# ActuatorCan.net
KiCad netlist of a schematic drawn in Altium Designer
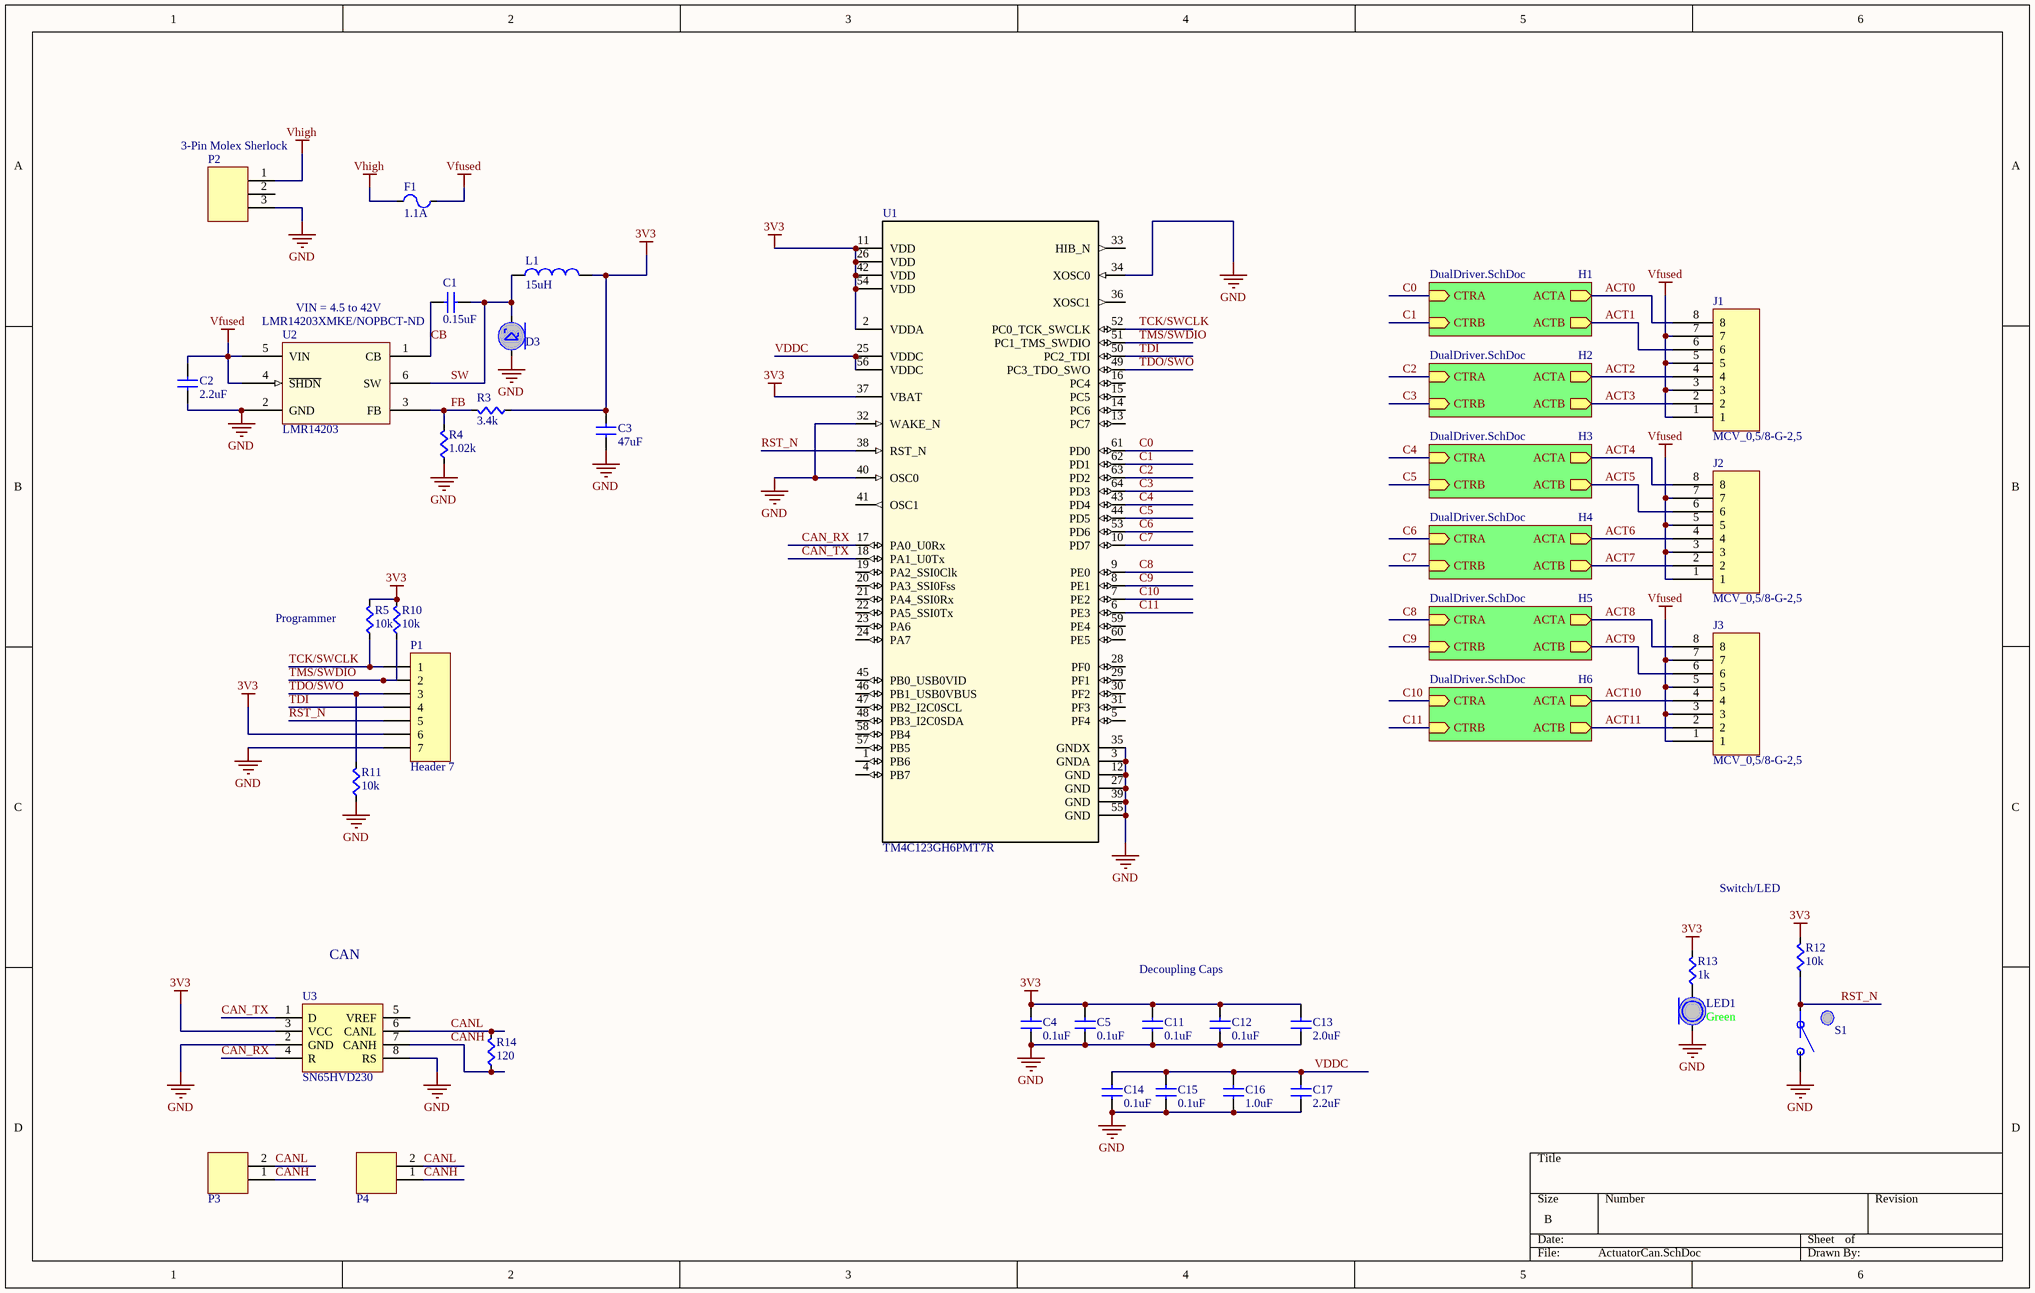
[diagram p0: ActuatorCan.SchDoc]

(export (version "E")
  (design (tool "Eeschema 10.0.6"))
  (components
    (comp (ref "C1")
      (value "0.15uF")
      (footprint "CAPC0603")
      (fields (field (name "Comment") "Cap"))
      (libsource (lib "Passives") (part "Cap"))
    )
    (comp (ref "C2")
      (value "2.2uF")
      (footprint "CAPC0805")
      (fields (field (name "Comment") "Cap"))
      (libsource (lib "Passives") (part "Cap"))
    )
    (comp (ref "C3")
      (value "47uF")
      (footprint "CAPC1206")
      (fields (field (name "Comment") "Cap"))
      (libsource (lib "Passives") (part "Cap"))
    )
    (comp (ref "C4")
      (value "0.1uF")
      (footprint "CAPC0603")
      (fields (field (name "Comment") "Cap"))
      (libsource (lib "SubjuGator8") (part "Cap"))
    )
    (comp (ref "C5")
      (value "0.1uF")
      (footprint "CAPC0603")
      (fields (field (name "Comment") "Cap"))
      (libsource (lib "SubjuGator8") (part "Cap"))
    )
    (comp (ref "C11")
      (value "0.1uF")
      (footprint "CAPC0603")
      (fields (field (name "Comment") "Cap"))
      (libsource (lib "SubjuGator8") (part "Cap"))
    )
    (comp (ref "C12")
      (value "0.1uF")
      (footprint "CAPC0603")
      (fields (field (name "Comment") "Cap"))
      (libsource (lib "SubjuGator8") (part "Cap"))
    )
    (comp (ref "C13")
      (value "2.0uF")
      (footprint "CAPC0603")
      (fields (field (name "Comment") "Cap"))
      (libsource (lib "SubjuGator8") (part "Cap"))
    )
    (comp (ref "C14")
      (value "0.1uF")
      (footprint "CAPC0603")
      (fields (field (name "Comment") "Cap"))
      (libsource (lib "SubjuGator8") (part "Cap"))
    )
    (comp (ref "C15")
      (value "0.1uF")
      (footprint "CAPC0603")
      (fields (field (name "Comment") "Cap"))
      (libsource (lib "SubjuGator8") (part "Cap"))
    )
    (comp (ref "C16")
      (value "1.0uF")
      (footprint "CAPC0603")
      (fields (field (name "Comment") "Cap"))
      (libsource (lib "SubjuGator8") (part "Cap"))
    )
    (comp (ref "C17")
      (value "2.2uF")
      (footprint "CAPC0603")
      (fields (field (name "Comment") "Cap"))
      (libsource (lib "SubjuGator8") (part "Cap"))
    )
    (comp (ref "D3")
      (value "Schottky")
      (footprint "1N5819HW-7-F")
      (description "Schottky Diode Template")
      (libsource (lib "Semiconductors") (part "Schottky"))
    )
    (comp (ref "F1")
      (value "1.1A")
      (footprint "PTC7451X11N")
      (fields (field (name "Comment") "PTC Fuse"))
      (libsource (lib "Passives") (part "PTC_Fuse"))
    )
    (comp (ref "J1")
      (value "MCV_0,5/8-G-2,5")
      (footprint "MCV_0,5/8-G-2,5")
      (description "CONN TERM BLOCK 2.50MM 8POS, Vertical, Through-Hole, 4A")
      (libsource (lib "Connectors") (part "MCV_0,5/8-G-2,5"))
    )
    (comp (ref "J2")
      (value "MCV_0,5/8-G-2,5")
      (footprint "MCV_0,5/8-G-2,5")
      (description "CONN TERM BLOCK 2.50MM 8POS, Vertical, Through-Hole, 4A")
      (libsource (lib "Connectors") (part "MCV_0,5/8-G-2,5"))
    )
    (comp (ref "J3")
      (value "MCV_0,5/8-G-2,5")
      (footprint "MCV_0,5/8-G-2,5")
      (description "CONN TERM BLOCK 2.50MM 8POS, Vertical, Through-Hole, 4A")
      (libsource (lib "Connectors") (part "MCV_0,5/8-G-2,5"))
    )
    (comp (ref "L1")
      (value "Inductor")
      (footprint "NS10165T150MNA")
      (fields (field (name "INDUCTANCE") "15uH"))
      (libsource (lib "Passives") (part "Inductor"))
    )
    (comp (ref "LED1")
      (value "LED")
      (footprint "LED0603")
      (fields (field (name "COLOR") "Green"))
      (libsource (lib "SubjuGator8") (part "LED"))
    )
    (comp (ref "P1")
      (value "Header 7")
      (footprint "HDR1X7")
      (description "Header, 7-Pin")
      (fields (field (name "PUBLISHER") "Altium Limited"))
      (libsource (lib "Miscellaneous Connectors") (part "Header 7"))
    )
    (comp (ref "P2")
      (value "3-Pin Molex Sherlock")
      (footprint "MOLEX-HDR-1X3-SHERLOCK-VERT")
      (libsource (lib "SubjuGator8") (part "MOLEX-HDR-1x3-SHERLOCK_VERT"))
    )
    (comp (ref "P3")
      (value "2-pin Horz Sherlock")
      (footprint "MOLEX-HDR-1X2-SHERLOCK-HORZ")
      (fields
        (field (name "MANUFACTURER PART NUMBER") "0353630260")
        (field (name "MANUFACTURER") "Molex Inc")
      )
      (libsource (lib "SubjuGator8") (part "MOLEX-HDR-1x2-SHERLOCK_RA"))
    )
    (comp (ref "P4")
      (value "2-pin Horz Sherlock")
      (footprint "MOLEX-HDR-1X2-SHERLOCK-HORZ")
      (fields
        (field (name "MANUFACTURER PART NUMBER") "0353630260")
        (field (name "MANUFACTURER") "Molex Inc")
      )
      (libsource (lib "SubjuGator8") (part "MOLEX-HDR-1x2-SHERLOCK_RA"))
    )
    (comp (ref "R3")
      (value "3.4k")
      (footprint "RES0603")
      (fields (field (name "Comment") "Res"))
      (libsource (lib "Passives") (part "Res"))
    )
    (comp (ref "R4")
      (value "1.02k")
      (footprint "RES0603")
      (fields (field (name "Comment") "Res"))
      (libsource (lib "Passives") (part "Res"))
    )
    (comp (ref "R5")
      (value "10k")
      (footprint "RES0603")
      (fields (field (name "Comment") "Res"))
      (libsource (lib "SubjuGator8") (part "Res"))
    )
    (comp (ref "R10")
      (value "10k")
      (footprint "RES0603")
      (fields (field (name "Comment") "Res"))
      (libsource (lib "SubjuGator8") (part "Res"))
    )
    (comp (ref "R11")
      (value "10k")
      (footprint "RES0603")
      (fields (field (name "Comment") "Res"))
      (libsource (lib "SubjuGator8") (part "Res"))
    )
    (comp (ref "R12")
      (value "10k")
      (footprint "RES0603")
      (fields (field (name "Comment") "Res"))
      (libsource (lib "SubjuGator8") (part "Res"))
    )
    (comp (ref "R13")
      (value "1k")
      (footprint "RES0603")
      (fields (field (name "Comment") "Res"))
      (libsource (lib "SubjuGator8") (part "Res"))
    )
    (comp (ref "R14")
      (value "120")
      (footprint "RES0603")
      (fields (field (name "Comment") "Res"))
      (libsource (lib "SubjuGator8") (part "Res"))
    )
    (comp (ref "S1")
      (value "Button")
      (footprint "PTS645xxxxSMTR92")
      (description "SPST Button")
      (libsource (lib "SubjuGator8") (part "Button"))
    )
    (comp (ref "U1")
      (value "TM4C123GH6PMT7R")
      (footprint "PM0064A_N")
      (description "Imported")
      (fields
        (field (name "PARTNUMBER") "TM4C123GH6PMTR")
        (field (name "ALTERNATE_PARTNUMBER") "TM4C123GH6PMT")
      )
      (libsource (lib "2018-10-31_17-53-54") (part "TM4C123GH6PMT7R"))
    )
    (comp (ref "U2")
      (value "LMR14203")
      (footprint "SOT95P280X110-6N")
      (description "Simple Switcher 42Vin 0.3A Step-Down Voltage Regulator")
      (fields (field (name "SUPPLIER PART NUMBER 1") "LMR14203XMKE/NOPBCT-ND"))
      (libsource (lib "ICs") (part "LMR14203"))
    )
    (comp (ref "U3")
      (value "SN65HVD230")
      (footprint "SOIC-8pin")
      (description "3.3V CAN Bus Transceiver")
      (libsource (lib "SubjuGator8") (part "SN65HVD230"))
    )
  )
  (nets
    (net (code "1") (name "/ACT0") (class "Default")
      (node (ref "J1") (pin "8") (pinfunction "8_8") (pintype "passive"))
    )
    (net (code "2") (name "/ACT1") (class "Default")
      (node (ref "J1") (pin "6") (pinfunction "6_6") (pintype "passive"))
    )
    (net (code "3") (name "/ACT2") (class "Default")
      (node (ref "J1") (pin "4") (pinfunction "4_4") (pintype "passive"))
    )
    (net (code "4") (name "/ACT3") (class "Default")
      (node (ref "J1") (pin "2") (pinfunction "2_2") (pintype "passive"))
    )
    (net (code "5") (name "/ACT4") (class "Default")
      (node (ref "J2") (pin "8") (pinfunction "8_8") (pintype "passive"))
    )
    (net (code "6") (name "/ACT5") (class "Default")
      (node (ref "J2") (pin "6") (pinfunction "6_6") (pintype "passive"))
    )
    (net (code "7") (name "/ACT6") (class "Default")
      (node (ref "J2") (pin "4") (pinfunction "4_4") (pintype "passive"))
    )
    (net (code "8") (name "/ACT7") (class "Default")
      (node (ref "J2") (pin "2") (pinfunction "2_2") (pintype "passive"))
    )
    (net (code "9") (name "/ACT8") (class "Default")
      (node (ref "J3") (pin "8") (pinfunction "8_8") (pintype "passive"))
    )
    (net (code "10") (name "/ACT9") (class "Default")
      (node (ref "J3") (pin "6") (pinfunction "6_6") (pintype "passive"))
    )
    (net (code "11") (name "/ACT10") (class "Default")
      (node (ref "J3") (pin "4") (pinfunction "4_4") (pintype "passive"))
    )
    (net (code "12") (name "/ACT11") (class "Default")
      (node (ref "J3") (pin "2") (pinfunction "2_2") (pintype "passive"))
    )
    (net (code "13") (name "/C0") (class "Default")
      (node (ref "U1") (pin "61") (pinfunction "PD0_61") (pintype "bidirectional"))
    )
    (net (code "14") (name "/C1") (class "Default")
      (node (ref "U1") (pin "62") (pinfunction "PD1_62") (pintype "bidirectional"))
    )
    (net (code "15") (name "/C2") (class "Default")
      (node (ref "U1") (pin "63") (pinfunction "PD2_63") (pintype "bidirectional"))
    )
    (net (code "16") (name "/C3") (class "Default")
      (node (ref "U1") (pin "64") (pinfunction "PD3_64") (pintype "bidirectional"))
    )
    (net (code "17") (name "/C4") (class "Default")
      (node (ref "U1") (pin "43") (pinfunction "PD4_43") (pintype "bidirectional"))
    )
    (net (code "18") (name "/C5") (class "Default")
      (node (ref "U1") (pin "44") (pinfunction "PD5_44") (pintype "bidirectional"))
    )
    (net (code "19") (name "/C6") (class "Default")
      (node (ref "U1") (pin "53") (pinfunction "PD6_53") (pintype "bidirectional"))
    )
    (net (code "20") (name "/C7") (class "Default")
      (node (ref "U1") (pin "10") (pinfunction "PD7_10") (pintype "bidirectional"))
    )
    (net (code "21") (name "/C8") (class "Default")
      (node (ref "U1") (pin "9") (pinfunction "PE0_9") (pintype "bidirectional"))
    )
    (net (code "22") (name "/C9") (class "Default")
      (node (ref "U1") (pin "8") (pinfunction "PE1_8") (pintype "bidirectional"))
    )
    (net (code "23") (name "/C10") (class "Default")
      (node (ref "U1") (pin "7") (pinfunction "PE2_7") (pintype "bidirectional"))
    )
    (net (code "24") (name "/C11") (class "Default")
      (node (ref "U1") (pin "6") (pinfunction "PE3_6") (pintype "bidirectional"))
    )
    (net (code "25") (name "/CANH") (class "Default")
      (node (ref "P3") (pin "1") (pinfunction "1_1") (pintype "passive"))
      (node (ref "P4") (pin "1") (pinfunction "1_1") (pintype "passive"))
      (node (ref "R14") (pin "2") (pinfunction "B_2") (pintype "passive"))
      (node (ref "U3") (pin "7") (pinfunction "CANH_7") (pintype "passive"))
    )
    (net (code "26") (name "/CANL") (class "Default")
      (node (ref "P3") (pin "2") (pinfunction "2_2") (pintype "passive"))
      (node (ref "P4") (pin "2") (pinfunction "2_2") (pintype "passive"))
      (node (ref "R14") (pin "1") (pinfunction "A_1") (pintype "passive"))
      (node (ref "U3") (pin "6") (pinfunction "CANL_6") (pintype "passive"))
    )
    (net (code "27") (name "/CAN_RX") (class "Default")
      (node (ref "U1") (pin "17") (pinfunction "PA0_U0Rx_17") (pintype "bidirectional"))
      (node (ref "U3") (pin "4") (pinfunction "R_4") (pintype "passive"))
    )
    (net (code "28") (name "/CAN_TX") (class "Default")
      (node (ref "U1") (pin "18") (pinfunction "PA1_U0Tx_18") (pintype "bidirectional"))
      (node (ref "U3") (pin "1") (pinfunction "D_1") (pintype "passive"))
    )
    (net (code "29") (name "/CB") (class "Default")
      (node (ref "C1") (pin "1") (pinfunction "A_1") (pintype "passive"))
      (node (ref "U2") (pin "1") (pinfunction "CB_1") (pintype "passive"))
    )
    (net (code "30") (name "/FB") (class "Default")
      (node (ref "R3") (pin "1") (pinfunction "A_1") (pintype "passive"))
      (node (ref "R4") (pin "1") (pinfunction "A_1") (pintype "passive"))
      (node (ref "U2") (pin "3") (pinfunction "FB_3") (pintype "passive"))
    )
    (net (code "31") (name "/RST_N") (class "Default")
      (node (ref "P1") (pin "5") (pinfunction "5_5") (pintype "passive"))
      (node (ref "R12") (pin "2") (pinfunction "B_2") (pintype "passive"))
      (node (ref "S1") (pin "A") (pinfunction "A_A") (pintype "passive"))
      (node (ref "U1") (pin "38") (pinfunction "RST_N_38") (pintype "input"))
    )
    (net (code "32") (name "/SW") (class "Default")
      (node (ref "C1") (pin "2") (pinfunction "B_2") (pintype "passive"))
      (node (ref "D3") (pin "C") (pinfunction "C_C") (pintype "passive"))
      (node (ref "L1") (pin "1") (pinfunction "A_1") (pintype "passive"))
      (node (ref "U2") (pin "6") (pinfunction "SW_6") (pintype "passive"))
    )
    (net (code "33") (name "/TCK{slash}SWCLK") (class "Default")
      (node (ref "P1") (pin "1") (pinfunction "1_1") (pintype "passive"))
      (node (ref "R5") (pin "2") (pinfunction "B_2") (pintype "passive"))
      (node (ref "U1") (pin "52") (pinfunction "PC0_TCK_SWCLK_52") (pintype "bidirectional"))
    )
    (net (code "34") (name "/TDI") (class "Default")
      (node (ref "P1") (pin "4") (pinfunction "4_4") (pintype "passive"))
      (node (ref "U1") (pin "50") (pinfunction "PC2_TDI_50") (pintype "bidirectional"))
    )
    (net (code "35") (name "/TDO{slash}SWO") (class "Default")
      (node (ref "P1") (pin "3") (pinfunction "3_3") (pintype "passive"))
      (node (ref "R11") (pin "1") (pinfunction "A_1") (pintype "passive"))
      (node (ref "U1") (pin "49") (pinfunction "PC3_TDO_SWO_49") (pintype "bidirectional"))
    )
    (net (code "36") (name "/TMS{slash}SWDIO") (class "Default")
      (node (ref "P1") (pin "2") (pinfunction "2_2") (pintype "passive"))
      (node (ref "R10") (pin "2") (pinfunction "B_2") (pintype "passive"))
      (node (ref "U1") (pin "51") (pinfunction "PC1_TMS_SWDIO_51") (pintype "bidirectional"))
    )
    (net (code "37") (name "/VDDC") (class "Default")
      (node (ref "C14") (pin "1") (pinfunction "A_1") (pintype "passive"))
      (node (ref "C15") (pin "1") (pinfunction "A_1") (pintype "passive"))
      (node (ref "C16") (pin "1") (pinfunction "A_1") (pintype "passive"))
      (node (ref "C17") (pin "1") (pinfunction "A_1") (pintype "passive"))
      (node (ref "U1") (pin "25") (pinfunction "VDDC_25") (pintype "power_in"))
      (node (ref "U1") (pin "56") (pinfunction "VDDC_56") (pintype "power_in"))
    )
    (net (code "38") (name "3V3") (class "Default")
      (node (ref "C11") (pin "1") (pinfunction "A_1") (pintype "passive"))
      (node (ref "C12") (pin "1") (pinfunction "A_1") (pintype "passive"))
      (node (ref "C13") (pin "1") (pinfunction "A_1") (pintype "passive"))
      (node (ref "C3") (pin "2") (pinfunction "B_2") (pintype "passive"))
      (node (ref "C4") (pin "1") (pinfunction "A_1") (pintype "passive"))
      (node (ref "C5") (pin "1") (pinfunction "A_1") (pintype "passive"))
      (node (ref "L1") (pin "2") (pinfunction "B_2") (pintype "passive"))
      (node (ref "P1") (pin "6") (pinfunction "6_6") (pintype "passive"))
      (node (ref "R10") (pin "1") (pinfunction "A_1") (pintype "passive"))
      (node (ref "R12") (pin "1") (pinfunction "A_1") (pintype "passive"))
      (node (ref "R13") (pin "1") (pinfunction "A_1") (pintype "passive"))
      (node (ref "R3") (pin "2") (pinfunction "B_2") (pintype "passive"))
      (node (ref "R5") (pin "1") (pinfunction "A_1") (pintype "passive"))
      (node (ref "U1") (pin "11") (pinfunction "VDD_11") (pintype "power_in"))
      (node (ref "U1") (pin "2") (pinfunction "VDDA_2") (pintype "power_in"))
      (node (ref "U1") (pin "26") (pinfunction "VDD_26") (pintype "power_in"))
      (node (ref "U1") (pin "37") (pinfunction "VBAT_37") (pintype "power_in"))
      (node (ref "U1") (pin "42") (pinfunction "VDD_42") (pintype "power_in"))
      (node (ref "U1") (pin "54") (pinfunction "VDD_54") (pintype "power_in"))
      (node (ref "U3") (pin "3") (pinfunction "VCC_3") (pintype "passive"))
    )
    (net (code "39") (name "GND") (class "Default")
      (node (ref "C11") (pin "2") (pinfunction "B_2") (pintype "passive"))
      (node (ref "C12") (pin "2") (pinfunction "B_2") (pintype "passive"))
      (node (ref "C13") (pin "2") (pinfunction "B_2") (pintype "passive"))
      (node (ref "C14") (pin "2") (pinfunction "B_2") (pintype "passive"))
      (node (ref "C15") (pin "2") (pinfunction "B_2") (pintype "passive"))
      (node (ref "C16") (pin "2") (pinfunction "B_2") (pintype "passive"))
      (node (ref "C17") (pin "2") (pinfunction "B_2") (pintype "passive"))
      (node (ref "C2") (pin "1") (pinfunction "A_1") (pintype "passive"))
      (node (ref "C3") (pin "1") (pinfunction "A_1") (pintype "passive"))
      (node (ref "C4") (pin "2") (pinfunction "B_2") (pintype "passive"))
      (node (ref "C5") (pin "2") (pinfunction "B_2") (pintype "passive"))
      (node (ref "D3") (pin "A") (pinfunction "A_A") (pintype "passive"))
      (node (ref "LED1") (pin "C") (pinfunction "C_C") (pintype "passive"))
      (node (ref "P1") (pin "7") (pinfunction "7_7") (pintype "passive"))
      (node (ref "P2") (pin "3") (pinfunction "3_3") (pintype "passive"))
      (node (ref "R11") (pin "2") (pinfunction "B_2") (pintype "passive"))
      (node (ref "R4") (pin "2") (pinfunction "B_2") (pintype "passive"))
      (node (ref "S1") (pin "B") (pinfunction "B_B") (pintype "passive"))
      (node (ref "U1") (pin "12") (pinfunction "GND_12") (pintype "power_in"))
      (node (ref "U1") (pin "27") (pinfunction "GND_27") (pintype "power_in"))
      (node (ref "U1") (pin "3") (pinfunction "GNDA_3") (pintype "power_in"))
      (node (ref "U1") (pin "32") (pinfunction "WAKE_N_32") (pintype "input"))
      (node (ref "U1") (pin "34") (pinfunction "XOSC0_34") (pintype "input"))
      (node (ref "U1") (pin "35") (pinfunction "GNDX_35") (pintype "power_in"))
      (node (ref "U1") (pin "39") (pinfunction "GND_39") (pintype "power_in"))
      (node (ref "U1") (pin "40") (pinfunction "OSC0_40") (pintype "input"))
      (node (ref "U1") (pin "55") (pinfunction "GND_55") (pintype "power_in"))
      (node (ref "U2") (pin "2") (pinfunction "GND_2") (pintype "power_in"))
      (node (ref "U3") (pin "2") (pinfunction "GND_2") (pintype "passive"))
      (node (ref "U3") (pin "8") (pinfunction "RS_8") (pintype "passive"))
    )
    (net (code "40") (name "Net-(R13-B)") (class "Default")
      (node (ref "LED1") (pin "A") (pinfunction "A_A") (pintype "passive"))
      (node (ref "R13") (pin "2") (pinfunction "B_2") (pintype "passive"))
    )
    (net (code "41") (name "Vfused") (class "Default")
      (node (ref "C2") (pin "2") (pinfunction "B_2") (pintype "passive"))
      (node (ref "F1") (pin "2") (pinfunction "B_2") (pintype "passive"))
      (node (ref "J1") (pin "1") (pinfunction "1_1") (pintype "passive"))
      (node (ref "J1") (pin "3") (pinfunction "3_3") (pintype "passive"))
      (node (ref "J1") (pin "5") (pinfunction "5_5") (pintype "passive"))
      (node (ref "J1") (pin "7") (pinfunction "7_7") (pintype "passive"))
      (node (ref "J2") (pin "1") (pinfunction "1_1") (pintype "passive"))
      (node (ref "J2") (pin "3") (pinfunction "3_3") (pintype "passive"))
      (node (ref "J2") (pin "5") (pinfunction "5_5") (pintype "passive"))
      (node (ref "J2") (pin "7") (pinfunction "7_7") (pintype "passive"))
      (node (ref "J3") (pin "1") (pinfunction "1_1") (pintype "passive"))
      (node (ref "J3") (pin "3") (pinfunction "3_3") (pintype "passive"))
      (node (ref "J3") (pin "5") (pinfunction "5_5") (pintype "passive"))
      (node (ref "J3") (pin "7") (pinfunction "7_7") (pintype "passive"))
      (node (ref "U2") (pin "4") (pinfunction "~{SHDN}_4") (pintype "input"))
      (node (ref "U2") (pin "5") (pinfunction "VIN_5") (pintype "passive"))
    )
    (net (code "42") (name "Vhigh") (class "Default")
      (node (ref "F1") (pin "1") (pinfunction "A_1") (pintype "passive"))
      (node (ref "P2") (pin "1") (pinfunction "1_1") (pintype "passive"))
    )
    (net (code "43") (name "unconnected-(P2-Pad2)") (class "Default")
      (node (ref "P2") (pin "2") (pinfunction "2_2") (pintype "passive"))
    )
    (net (code "44") (name "unconnected-(U1-HIB_N-Pad33)") (class "Default")
      (node (ref "U1") (pin "33") (pinfunction "HIB_N_33") (pintype "output"))
    )
    (net (code "45") (name "unconnected-(U1-OSC1-Pad41)") (class "Default")
      (node (ref "U1") (pin "41") (pinfunction "OSC1_41") (pintype "output"))
    )
    (net (code "46") (name "unconnected-(U1-PA2_SSI0Clk-Pad19)") (class "Default")
      (node (ref "U1") (pin "19") (pinfunction "PA2_SSI0Clk_19") (pintype "bidirectional"))
    )
    (net (code "47") (name "unconnected-(U1-PA3_SSI0Fss-Pad20)") (class "Default")
      (node (ref "U1") (pin "20") (pinfunction "PA3_SSI0Fss_20") (pintype "bidirectional"))
    )
    (net (code "48") (name "unconnected-(U1-PA4_SSI0Rx-Pad21)") (class "Default")
      (node (ref "U1") (pin "21") (pinfunction "PA4_SSI0Rx_21") (pintype "bidirectional"))
    )
    (net (code "49") (name "unconnected-(U1-PA5_SSI0Tx-Pad22)") (class "Default")
      (node (ref "U1") (pin "22") (pinfunction "PA5_SSI0Tx_22") (pintype "bidirectional"))
    )
    (net (code "50") (name "unconnected-(U1-PA6-Pad23)") (class "Default")
      (node (ref "U1") (pin "23") (pinfunction "PA6_23") (pintype "bidirectional"))
    )
    (net (code "51") (name "unconnected-(U1-PA7-Pad24)") (class "Default")
      (node (ref "U1") (pin "24") (pinfunction "PA7_24") (pintype "bidirectional"))
    )
    (net (code "52") (name "unconnected-(U1-PB0_USB0VID-Pad45)") (class "Default")
      (node (ref "U1") (pin "45") (pinfunction "PB0_USB0VID_45") (pintype "bidirectional"))
    )
    (net (code "53") (name "unconnected-(U1-PB1_USB0VBUS-Pad46)") (class "Default")
      (node (ref "U1") (pin "46") (pinfunction "PB1_USB0VBUS_46") (pintype "bidirectional"))
    )
    (net (code "54") (name "unconnected-(U1-PB2_I2C0SCL-Pad47)") (class "Default")
      (node (ref "U1") (pin "47") (pinfunction "PB2_I2C0SCL_47") (pintype "bidirectional"))
    )
    (net (code "55") (name "unconnected-(U1-PB3_I2C0SDA-Pad48)") (class "Default")
      (node (ref "U1") (pin "48") (pinfunction "PB3_I2C0SDA_48") (pintype "bidirectional"))
    )
    (net (code "56") (name "unconnected-(U1-PB4-Pad58)") (class "Default")
      (node (ref "U1") (pin "58") (pinfunction "PB4_58") (pintype "bidirectional"))
    )
    (net (code "57") (name "unconnected-(U1-PB5-Pad57)") (class "Default")
      (node (ref "U1") (pin "57") (pinfunction "PB5_57") (pintype "bidirectional"))
    )
    (net (code "58") (name "unconnected-(U1-PB6-Pad1)") (class "Default")
      (node (ref "U1") (pin "1") (pinfunction "PB6_1") (pintype "bidirectional"))
    )
    (net (code "59") (name "unconnected-(U1-PB7-Pad4)") (class "Default")
      (node (ref "U1") (pin "4") (pinfunction "PB7_4") (pintype "bidirectional"))
    )
    (net (code "60") (name "unconnected-(U1-PC4-Pad16)") (class "Default")
      (node (ref "U1") (pin "16") (pinfunction "PC4_16") (pintype "bidirectional"))
    )
    (net (code "61") (name "unconnected-(U1-PC5-Pad15)") (class "Default")
      (node (ref "U1") (pin "15") (pinfunction "PC5_15") (pintype "bidirectional"))
    )
    (net (code "62") (name "unconnected-(U1-PC6-Pad14)") (class "Default")
      (node (ref "U1") (pin "14") (pinfunction "PC6_14") (pintype "bidirectional"))
    )
    (net (code "63") (name "unconnected-(U1-PC7-Pad13)") (class "Default")
      (node (ref "U1") (pin "13") (pinfunction "PC7_13") (pintype "bidirectional"))
    )
    (net (code "64") (name "unconnected-(U1-PE4-Pad59)") (class "Default")
      (node (ref "U1") (pin "59") (pinfunction "PE4_59") (pintype "bidirectional"))
    )
    (net (code "65") (name "unconnected-(U1-PE5-Pad60)") (class "Default")
      (node (ref "U1") (pin "60") (pinfunction "PE5_60") (pintype "bidirectional"))
    )
    (net (code "66") (name "unconnected-(U1-PF0-Pad28)") (class "Default")
      (node (ref "U1") (pin "28") (pinfunction "PF0_28") (pintype "bidirectional"))
    )
    (net (code "67") (name "unconnected-(U1-PF1-Pad29)") (class "Default")
      (node (ref "U1") (pin "29") (pinfunction "PF1_29") (pintype "bidirectional"))
    )
    (net (code "68") (name "unconnected-(U1-PF2-Pad30)") (class "Default")
      (node (ref "U1") (pin "30") (pinfunction "PF2_30") (pintype "bidirectional"))
    )
    (net (code "69") (name "unconnected-(U1-PF3-Pad31)") (class "Default")
      (node (ref "U1") (pin "31") (pinfunction "PF3_31") (pintype "bidirectional"))
    )
    (net (code "70") (name "unconnected-(U1-PF4-Pad5)") (class "Default")
      (node (ref "U1") (pin "5") (pinfunction "PF4_5") (pintype "bidirectional"))
    )
    (net (code "71") (name "unconnected-(U1-XOSC1-Pad36)") (class "Default")
      (node (ref "U1") (pin "36") (pinfunction "XOSC1_36") (pintype "output"))
    )
    (net (code "72") (name "unconnected-(U3-VREF-Pad5)") (class "Default")
      (node (ref "U3") (pin "5") (pinfunction "VREF_5") (pintype "passive"))
    )
  )
)
